# RGBMatrixHat.net
KiCad netlist of a schematic drawn in EAGLE
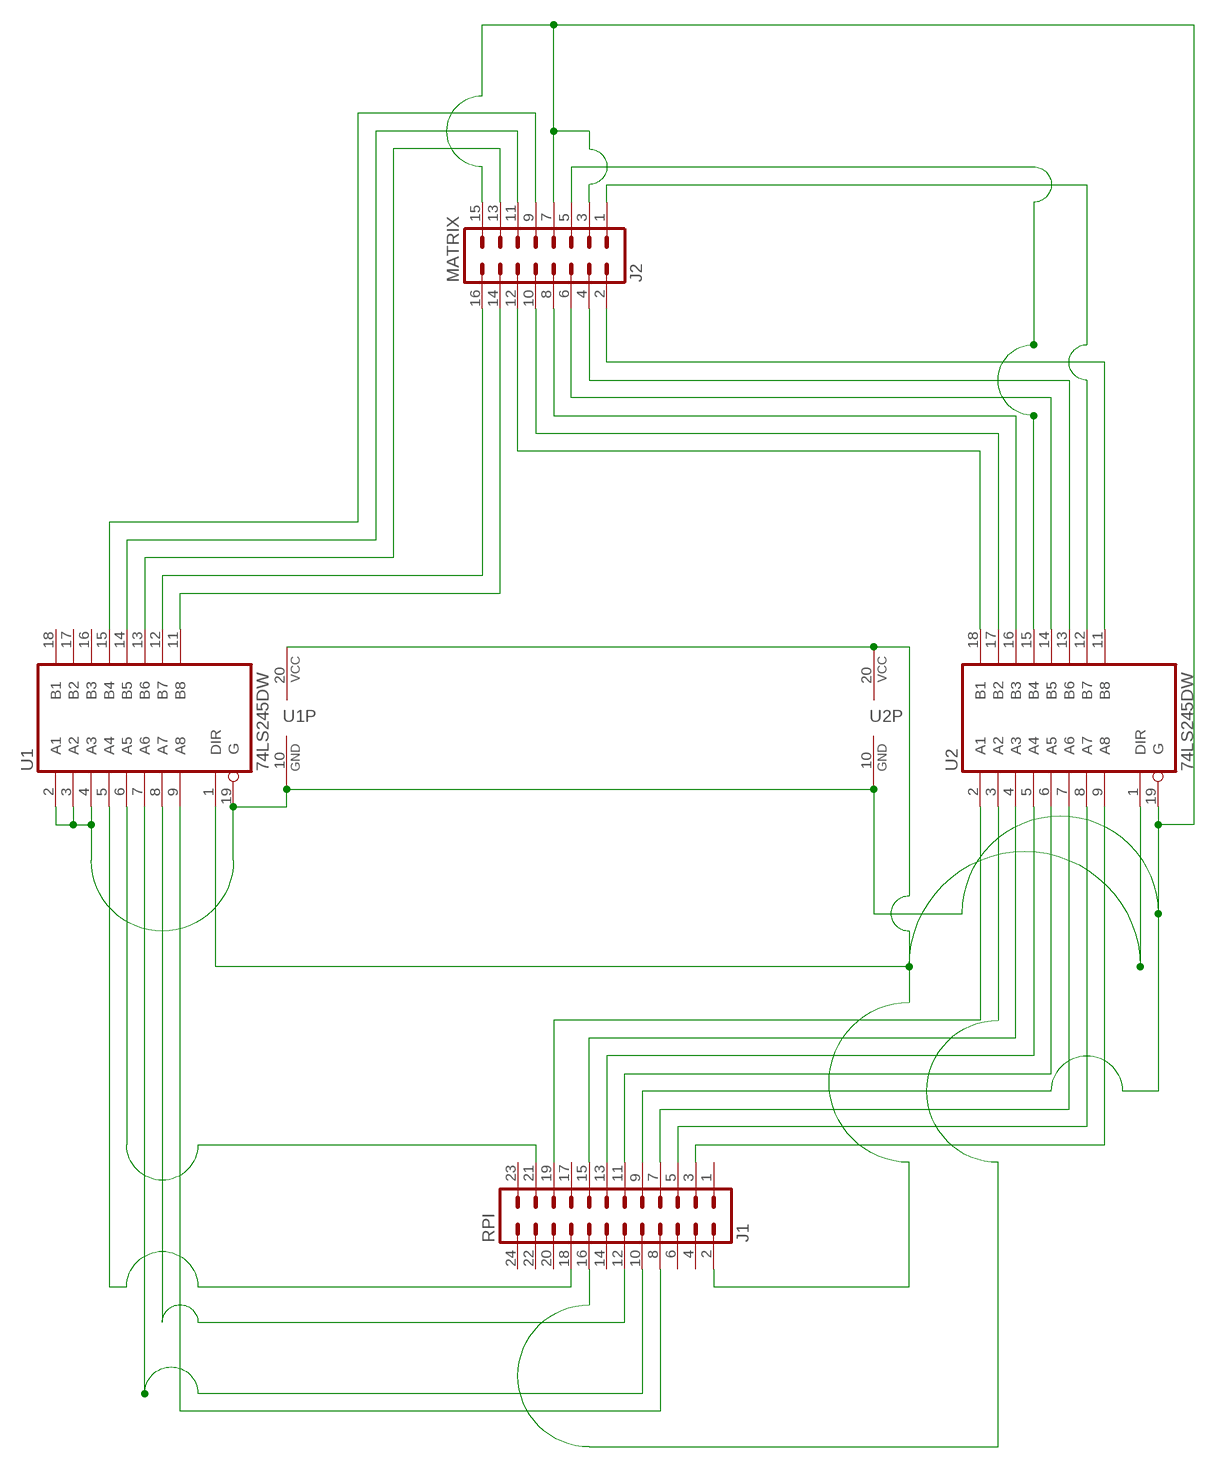
[diagram p0: schematic, sheet 1]

(export (version "E")
  (design (tool "Eeschema 10.0.6"))
  (components
    (comp (ref "MATRIX")
      (value "J2")
      (footprint "eagle-import:MA08-2")
      (libsource (lib "eagle-import") (part "MA08-2"))
    )
    (comp (ref "RPI")
      (value "J1")
      (footprint "eagle-import:MA12-2")
      (libsource (lib "eagle-import") (part "MA12-2"))
    )
    (comp (ref "U1")
      (value "74LS245DW")
      (footprint "eagle-import:SO20W")
      (libsource (lib "eagle-import") (part "74245DWLS"))
    )
    (comp (ref "U2")
      (value "74LS245DW")
      (footprint "eagle-import:SO20W")
      (libsource (lib "eagle-import") (part "74245DWLS"))
    )
  )
  (nets
    (net (code "1") (name "Net-(U1A-A1)") (class "Default")
      (node (ref "MATRIX") (pin "15") (pinfunction "15_15") (pintype "passive"))
      (node (ref "MATRIX") (pin "3") (pinfunction "3_3") (pintype "passive"))
      (node (ref "MATRIX") (pin "7") (pinfunction "7_7") (pintype "passive"))
      (node (ref "RPI") (pin "9") (pinfunction "9_9") (pintype "passive"))
      (node (ref "U1") (pin "10") (pinfunction "GND_10") (pintype "power_in"))
      (node (ref "U1") (pin "19") (pinfunction "G_19") (pintype "input"))
      (node (ref "U1") (pin "2") (pinfunction "A1_2") (pintype "bidirectional"))
      (node (ref "U1") (pin "3") (pinfunction "A2_3") (pintype "bidirectional"))
      (node (ref "U1") (pin "4") (pinfunction "A3_4") (pintype "bidirectional"))
      (node (ref "U2") (pin "10") (pinfunction "GND_10") (pintype "power_in"))
      (node (ref "U2") (pin "19") (pinfunction "G_19") (pintype "input"))
    )
    (net (code "2") (name "Net-(U1A-A4)") (class "Default")
      (node (ref "RPI") (pin "18") (pinfunction "18_18") (pintype "passive"))
      (node (ref "U1") (pin "5") (pinfunction "A4_5") (pintype "bidirectional"))
    )
    (net (code "3") (name "Net-(U1A-A5)") (class "Default")
      (node (ref "RPI") (pin "21") (pinfunction "21_21") (pintype "passive"))
      (node (ref "U1") (pin "6") (pinfunction "A5_6") (pintype "bidirectional"))
    )
    (net (code "4") (name "Net-(U1A-A6)") (class "Default")
      (node (ref "RPI") (pin "10") (pinfunction "10_10") (pintype "passive"))
      (node (ref "U1") (pin "7") (pinfunction "A6_7") (pintype "bidirectional"))
    )
    (net (code "5") (name "Net-(U1A-A7)") (class "Default")
      (node (ref "RPI") (pin "12") (pinfunction "12_12") (pintype "passive"))
      (node (ref "U1") (pin "8") (pinfunction "A7_8") (pintype "bidirectional"))
    )
    (net (code "6") (name "Net-(U1A-A8)") (class "Default")
      (node (ref "RPI") (pin "8") (pinfunction "8_8") (pintype "passive"))
      (node (ref "U1") (pin "9") (pinfunction "A8_9") (pintype "bidirectional"))
    )
    (net (code "7") (name "Net-(U1A-B4)") (class "Default")
      (node (ref "MATRIX") (pin "9") (pinfunction "9_9") (pintype "passive"))
      (node (ref "U1") (pin "15") (pinfunction "B4_15") (pintype "bidirectional"))
    )
    (net (code "8") (name "Net-(U1A-B5)") (class "Default")
      (node (ref "MATRIX") (pin "11") (pinfunction "11_11") (pintype "passive"))
      (node (ref "U1") (pin "14") (pinfunction "B5_14") (pintype "bidirectional"))
    )
    (net (code "9") (name "Net-(U1A-B6)") (class "Default")
      (node (ref "MATRIX") (pin "13") (pinfunction "13_13") (pintype "passive"))
      (node (ref "U1") (pin "13") (pinfunction "B6_13") (pintype "bidirectional"))
    )
    (net (code "10") (name "Net-(U1A-B7)") (class "Default")
      (node (ref "MATRIX") (pin "16") (pinfunction "16_16") (pintype "passive"))
      (node (ref "U1") (pin "12") (pinfunction "B7_12") (pintype "bidirectional"))
    )
    (net (code "11") (name "Net-(U1A-B8)") (class "Default")
      (node (ref "MATRIX") (pin "14") (pinfunction "14_14") (pintype "passive"))
      (node (ref "U1") (pin "11") (pinfunction "B8_11") (pintype "bidirectional"))
    )
    (net (code "12") (name "Net-(U1A-DIR)") (class "Default")
      (node (ref "RPI") (pin "2") (pinfunction "2_2") (pintype "passive"))
      (node (ref "U1") (pin "1") (pinfunction "DIR_1") (pintype "input"))
      (node (ref "U1") (pin "20") (pinfunction "VCC_20") (pintype "power_in"))
      (node (ref "U2") (pin "1") (pinfunction "DIR_1") (pintype "input"))
      (node (ref "U2") (pin "20") (pinfunction "VCC_20") (pintype "power_in"))
    )
    (net (code "13") (name "Net-(U2A-A1)") (class "Default")
      (node (ref "RPI") (pin "19") (pinfunction "19_19") (pintype "passive"))
      (node (ref "U2") (pin "2") (pinfunction "A1_2") (pintype "bidirectional"))
    )
    (net (code "14") (name "Net-(U2A-A2)") (class "Default")
      (node (ref "RPI") (pin "16") (pinfunction "16_16") (pintype "passive"))
      (node (ref "U2") (pin "3") (pinfunction "A2_3") (pintype "bidirectional"))
    )
    (net (code "15") (name "Net-(U2A-A3)") (class "Default")
      (node (ref "RPI") (pin "15") (pinfunction "15_15") (pintype "passive"))
      (node (ref "U2") (pin "4") (pinfunction "A3_4") (pintype "bidirectional"))
    )
    (net (code "16") (name "Net-(U2A-A4)") (class "Default")
      (node (ref "RPI") (pin "13") (pinfunction "13_13") (pintype "passive"))
      (node (ref "U2") (pin "5") (pinfunction "A4_5") (pintype "bidirectional"))
    )
    (net (code "17") (name "Net-(U2A-A5)") (class "Default")
      (node (ref "RPI") (pin "11") (pinfunction "11_11") (pintype "passive"))
      (node (ref "U2") (pin "6") (pinfunction "A5_6") (pintype "bidirectional"))
    )
    (net (code "18") (name "Net-(U2A-A6)") (class "Default")
      (node (ref "RPI") (pin "7") (pinfunction "7_7") (pintype "passive"))
      (node (ref "U2") (pin "7") (pinfunction "A6_7") (pintype "bidirectional"))
    )
    (net (code "19") (name "Net-(U2A-A7)") (class "Default")
      (node (ref "RPI") (pin "5") (pinfunction "5_5") (pintype "passive"))
      (node (ref "U2") (pin "8") (pinfunction "A7_8") (pintype "bidirectional"))
    )
    (net (code "20") (name "Net-(U2A-A8)") (class "Default")
      (node (ref "RPI") (pin "3") (pinfunction "3_3") (pintype "passive"))
      (node (ref "U2") (pin "9") (pinfunction "A8_9") (pintype "bidirectional"))
    )
    (net (code "21") (name "Net-(U2A-B1)") (class "Default")
      (node (ref "MATRIX") (pin "12") (pinfunction "12_12") (pintype "passive"))
      (node (ref "U2") (pin "18") (pinfunction "B1_18") (pintype "bidirectional"))
    )
    (net (code "22") (name "Net-(U2A-B2)") (class "Default")
      (node (ref "MATRIX") (pin "10") (pinfunction "10_10") (pintype "passive"))
      (node (ref "U2") (pin "17") (pinfunction "B2_17") (pintype "bidirectional"))
    )
    (net (code "23") (name "Net-(U2A-B3)") (class "Default")
      (node (ref "MATRIX") (pin "8") (pinfunction "8_8") (pintype "passive"))
      (node (ref "U2") (pin "16") (pinfunction "B3_16") (pintype "bidirectional"))
    )
    (net (code "24") (name "Net-(U2A-B4)") (class "Default")
      (node (ref "MATRIX") (pin "5") (pinfunction "5_5") (pintype "passive"))
      (node (ref "U2") (pin "15") (pinfunction "B4_15") (pintype "bidirectional"))
    )
    (net (code "25") (name "Net-(U2A-B5)") (class "Default")
      (node (ref "MATRIX") (pin "6") (pinfunction "6_6") (pintype "passive"))
      (node (ref "U2") (pin "14") (pinfunction "B5_14") (pintype "bidirectional"))
    )
    (net (code "26") (name "Net-(U2A-B6)") (class "Default")
      (node (ref "MATRIX") (pin "4") (pinfunction "4_4") (pintype "passive"))
      (node (ref "U2") (pin "13") (pinfunction "B6_13") (pintype "bidirectional"))
    )
    (net (code "27") (name "Net-(U2A-B7)") (class "Default")
      (node (ref "MATRIX") (pin "1") (pinfunction "1_1") (pintype "passive"))
      (node (ref "U2") (pin "12") (pinfunction "B7_12") (pintype "bidirectional"))
    )
    (net (code "28") (name "Net-(U2A-B8)") (class "Default")
      (node (ref "MATRIX") (pin "2") (pinfunction "2_2") (pintype "passive"))
      (node (ref "U2") (pin "11") (pinfunction "B8_11") (pintype "bidirectional"))
    )
    (net (code "29") (name "unconnected-(RPI-Pad1)") (class "Default")
      (node (ref "RPI") (pin "1") (pinfunction "1_1") (pintype "passive"))
    )
    (net (code "30") (name "unconnected-(RPI-Pad4)") (class "Default")
      (node (ref "RPI") (pin "4") (pinfunction "4_4") (pintype "passive"))
    )
    (net (code "31") (name "unconnected-(RPI-Pad6)") (class "Default")
      (node (ref "RPI") (pin "6") (pinfunction "6_6") (pintype "passive"))
    )
    (net (code "32") (name "unconnected-(RPI-Pad14)") (class "Default")
      (node (ref "RPI") (pin "14") (pinfunction "14_14") (pintype "passive"))
    )
    (net (code "33") (name "unconnected-(RPI-Pad17)") (class "Default")
      (node (ref "RPI") (pin "17") (pinfunction "17_17") (pintype "passive"))
    )
    (net (code "34") (name "unconnected-(RPI-Pad20)") (class "Default")
      (node (ref "RPI") (pin "20") (pinfunction "20_20") (pintype "passive"))
    )
    (net (code "35") (name "unconnected-(RPI-Pad22)") (class "Default")
      (node (ref "RPI") (pin "22") (pinfunction "22_22") (pintype "passive"))
    )
    (net (code "36") (name "unconnected-(RPI-Pad23)") (class "Default")
      (node (ref "RPI") (pin "23") (pinfunction "23_23") (pintype "passive"))
    )
    (net (code "37") (name "unconnected-(RPI-Pad24)") (class "Default")
      (node (ref "RPI") (pin "24") (pinfunction "24_24") (pintype "passive"))
    )
    (net (code "38") (name "unconnected-(U1A-B1-Pad18)") (class "Default")
      (node (ref "U1") (pin "18") (pinfunction "B1_18") (pintype "bidirectional"))
    )
    (net (code "39") (name "unconnected-(U1A-B2-Pad17)") (class "Default")
      (node (ref "U1") (pin "17") (pinfunction "B2_17") (pintype "bidirectional"))
    )
    (net (code "40") (name "unconnected-(U1A-B3-Pad16)") (class "Default")
      (node (ref "U1") (pin "16") (pinfunction "B3_16") (pintype "bidirectional"))
    )
  )
)
